# 1_P1.net
KiCad netlist of a schematic drawn in Altium Designer
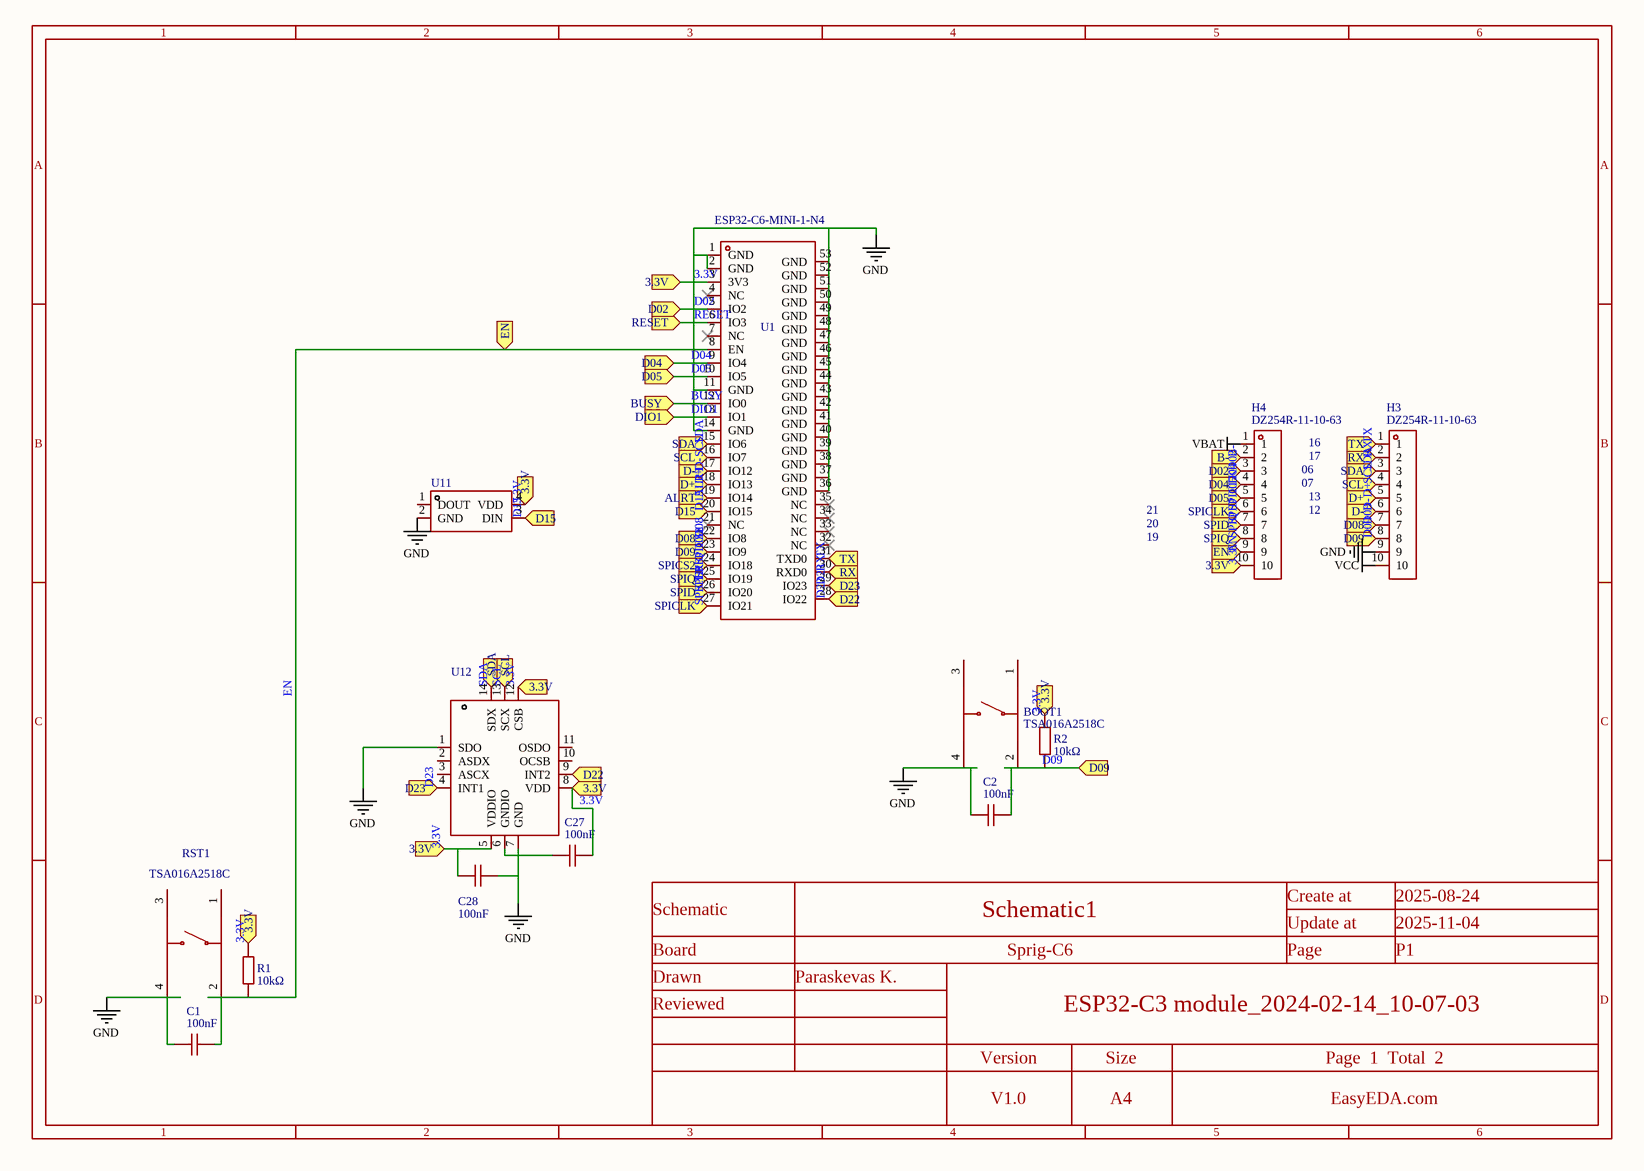
[diagram p0: 1_P1.schdoc]

(export (version "E")
  (design (tool "Eeschema 10.0.6"))
  (components
    (comp (ref "BOOT1")
      (value "TSA016A2518C")
      (footprint "SW-SMD_4P-L4.2-W3.3-P2.15-LS4.6")
      (fields (field (name "MANUFACTURER") "BZCN(博众电气)"))
      (libsource (lib "altium-import") (part "root_3_TSA016A2518C_"))
    )
    (comp (ref "C1")
      (value "100nF")
      (footprint "C0402")
      (fields
        (field (name "MANUFACTURER") "FH(风华)")
        (field (name "MANUFACTURER PART") "0402B104K160NT")
        (field (name "TOLERANCE") "±10%")
      )
      (libsource (lib "altium-import") (part "root_0_0402B104K160NT_"))
    )
    (comp (ref "C2")
      (value "100nF")
      (footprint "C0402")
      (fields
        (field (name "MANUFACTURER") "FH(风华)")
        (field (name "MANUFACTURER PART") "0402B104K160NT")
        (field (name "TOLERANCE") "±10%")
      )
      (libsource (lib "altium-import") (part "root_0_0402B104K160NT_"))
    )
    (comp (ref "C27")
      (value "100nF")
      (footprint "C0402")
      (fields
        (field (name "MANUFACTURER") "FH(风华)")
        (field (name "MANUFACTURER PART") "0402B104K160NT")
        (field (name "TOLERANCE") "±10%")
      )
      (libsource (lib "altium-import") (part "root_0_0402B104K160NT_"))
    )
    (comp (ref "C28")
      (value "100nF")
      (footprint "C0402")
      (fields
        (field (name "MANUFACTURER") "FH(风华)")
        (field (name "MANUFACTURER PART") "0402B104K160NT")
        (field (name "TOLERANCE") "±10%")
      )
      (libsource (lib "altium-import") (part "root_0_0402B104K160NT_"))
    )
    (comp (ref "H3")
      (value "DZ254R-11-10-63")
      (footprint "HDR-TH_10P-P2.54-V-M")
      (fields (field (name "MANUFACTURER") "DEALON(德艺隆)"))
      (libsource (lib "altium-import") (part "root_0_DZ254R-11-10-63_"))
    )
    (comp (ref "H4")
      (value "DZ254R-11-10-63")
      (footprint "HDR-TH_10P-P2.54-V-M")
      (fields (field (name "MANUFACTURER") "DEALON(德艺隆)"))
      (libsource (lib "altium-import") (part "root_0_DZ254R-11-10-63_"))
    )
    (comp (ref "R1")
      (value "10kΩ")
      (footprint "R0402")
      (fields
        (field (name "MANUFACTURER") "大毅科技")
        (field (name "MANUFACTURER PART") "RMS04FT1002")
        (field (name "TOLERANCE") "±1%")
      )
      (libsource (lib "altium-import") (part "root_1_RMS04FT1002_"))
    )
    (comp (ref "R2")
      (value "10kΩ")
      (footprint "R0402")
      (fields
        (field (name "MANUFACTURER") "大毅科技")
        (field (name "MANUFACTURER PART") "RMS04FT1002")
        (field (name "TOLERANCE") "±1%")
      )
      (libsource (lib "altium-import") (part "root_1_RMS04FT1002_"))
    )
    (comp (ref "RST1")
      (value "TSA016A2518C")
      (footprint "SW-SMD_4P-L4.2-W3.3-P2.15-LS4.6")
      (fields (field (name "MANUFACTURER") "BZCN(博众电气)"))
      (libsource (lib "altium-import") (part "root_3_TSA016A2518C_"))
    )
    (comp (ref "U1")
      (value "ESP32-C6-MINI-1-N4")
      (footprint "WIFIM-SMD_61P-L16.6-W13.2-P0.80-ESP32-C6-MINI-1-N4")
      (fields (field (name "MANUFACTURER") "ESPRESSIF(乐鑫)"))
      (libsource (lib "altium-import") (part "root_0_ESP32-C6-MINI-1-N4_"))
    )
    (comp (ref "U11")
      (value "SK6805D-EC2018")
      (footprint "LED-SMD_4P-L2.0-W1.8-BL_SK6805D")
      (fields (field (name "MANUFACTURER") "欧思科光电"))
      (libsource (lib "altium-import") (part "root_0_SK6805D-EC2018_"))
    )
    (comp (ref "U12")
      (value "BMI260")
      (footprint "LGA-14_L3.0-W2.5-P0.50-TL")
      (fields (field (name "MANUFACTURER") "Bosch(博世)"))
      (libsource (lib "altium-import") (part "root_0_BMI260_"))
    )
  )
  (nets
    (net (code "1") (name "/ALRT") (class "Default")
      (node (ref "U1") (pin "19") (pinfunction "IO14_19") (pintype "passive"))
    )
    (net (code "2") (name "/B-") (class "Default")
      (node (ref "H4") (pin "2") (pinfunction "2_2") (pintype "passive"))
    )
    (net (code "3") (name "/BUSY") (class "Default")
      (node (ref "U1") (pin "12") (pinfunction "IO0_12") (pintype "passive"))
    )
    (net (code "4") (name "/D+") (class "Default")
      (node (ref "H3") (pin "5") (pinfunction "5_5") (pintype "passive"))
      (node (ref "U1") (pin "18") (pinfunction "IO13_18") (pintype "passive"))
    )
    (net (code "5") (name "/D-") (class "Default")
      (node (ref "H3") (pin "6") (pinfunction "6_6") (pintype "passive"))
      (node (ref "U1") (pin "17") (pinfunction "IO12_17") (pintype "passive"))
    )
    (net (code "6") (name "/D04") (class "Default")
      (node (ref "H4") (pin "4") (pinfunction "4_4") (pintype "passive"))
      (node (ref "U1") (pin "9") (pinfunction "IO4_9") (pintype "passive"))
    )
    (net (code "7") (name "/D05") (class "Default")
      (node (ref "H4") (pin "5") (pinfunction "5_5") (pintype "passive"))
      (node (ref "U1") (pin "10") (pinfunction "IO5_10") (pintype "passive"))
    )
    (net (code "8") (name "/D08") (class "Default")
      (node (ref "H3") (pin "7") (pinfunction "7_7") (pintype "passive"))
      (node (ref "U1") (pin "22") (pinfunction "IO8_22") (pintype "passive"))
    )
    (net (code "9") (name "/D09") (class "Default")
      (node (ref "BOOT1") (pin "2") (pinfunction "2_2") (pintype "passive"))
      (node (ref "C2") (pin "2") (pinfunction "2_2") (pintype "passive"))
      (node (ref "H3") (pin "8") (pinfunction "8_8") (pintype "passive"))
      (node (ref "R2") (pin "1") (pinfunction "1_1") (pintype "passive"))
      (node (ref "U1") (pin "23") (pinfunction "IO9_23") (pintype "passive"))
    )
    (net (code "10") (name "/D15") (class "Default")
      (node (ref "U1") (pin "20") (pinfunction "IO15_20") (pintype "passive"))
      (node (ref "U11") (pin "3") (pinfunction "DIN_3") (pintype "passive"))
    )
    (net (code "11") (name "/D22") (class "Default")
      (node (ref "U1") (pin "28") (pinfunction "IO22_28") (pintype "passive"))
      (node (ref "U12") (pin "9") (pinfunction "INT2_9") (pintype "passive"))
    )
    (net (code "12") (name "/D23") (class "Default")
      (node (ref "U1") (pin "29") (pinfunction "IO23_29") (pintype "passive"))
      (node (ref "U12") (pin "4") (pinfunction "INT1_4") (pintype "passive"))
    )
    (net (code "13") (name "/DIO1") (class "Default")
      (node (ref "U1") (pin "13") (pinfunction "IO1_13") (pintype "passive"))
    )
    (net (code "14") (name "/EN") (class "Default")
      (node (ref "C1") (pin "2") (pinfunction "2_2") (pintype "passive"))
      (node (ref "H4") (pin "9") (pinfunction "9_9") (pintype "passive"))
      (node (ref "R1") (pin "1") (pinfunction "1_1") (pintype "passive"))
      (node (ref "RST1") (pin "2") (pinfunction "2_2") (pintype "passive"))
      (node (ref "U1") (pin "8") (pinfunction "EN_8") (pintype "passive"))
    )
    (net (code "15") (name "/RX") (class "Default")
      (node (ref "H3") (pin "2") (pinfunction "2_2") (pintype "passive"))
      (node (ref "U1") (pin "30") (pinfunction "RXD0_30") (pintype "passive"))
    )
    (net (code "16") (name "/SCL") (class "Default")
      (node (ref "H3") (pin "4") (pinfunction "4_4") (pintype "passive"))
      (node (ref "U1") (pin "16") (pinfunction "IO7_16") (pintype "passive"))
      (node (ref "U12") (pin "13") (pinfunction "SCX_13") (pintype "passive"))
    )
    (net (code "17") (name "/SDA") (class "Default")
      (node (ref "H3") (pin "3") (pinfunction "3_3") (pintype "passive"))
      (node (ref "U1") (pin "15") (pinfunction "IO6_15") (pintype "passive"))
      (node (ref "U12") (pin "14") (pinfunction "SDX_14") (pintype "passive"))
    )
    (net (code "18") (name "/SPICLK") (class "Default")
      (node (ref "H4") (pin "6") (pinfunction "6_6") (pintype "passive"))
      (node (ref "U1") (pin "27") (pinfunction "IO21_27") (pintype "passive"))
    )
    (net (code "19") (name "/SPICS2") (class "Default")
      (node (ref "U1") (pin "24") (pinfunction "IO18_24") (pintype "passive"))
    )
    (net (code "20") (name "/SPID") (class "Default")
      (node (ref "H4") (pin "7") (pinfunction "7_7") (pintype "passive"))
      (node (ref "U1") (pin "26") (pinfunction "IO20_26") (pintype "passive"))
    )
    (net (code "21") (name "/SPIQ") (class "Default")
      (node (ref "H4") (pin "8") (pinfunction "8_8") (pintype "passive"))
      (node (ref "U1") (pin "25") (pinfunction "IO19_25") (pintype "passive"))
    )
    (net (code "22") (name "/TX") (class "Default")
      (node (ref "H3") (pin "1") (pinfunction "1_1") (pintype "passive"))
      (node (ref "U1") (pin "31") (pinfunction "TXD0_31") (pintype "passive"))
    )
    (net (code "23") (name "GND") (class "Default")
      (node (ref "BOOT1") (pin "4") (pinfunction "4_4") (pintype "passive"))
      (node (ref "C1") (pin "1") (pinfunction "1_1") (pintype "passive"))
      (node (ref "C2") (pin "1") (pinfunction "1_1") (pintype "passive"))
      (node (ref "C27") (pin "1") (pinfunction "1_1") (pintype "passive"))
      (node (ref "C27") (pin "2") (pinfunction "2_2") (pintype "passive"))
      (node (ref "C28") (pin "1") (pinfunction "1_1") (pintype "passive"))
      (node (ref "C28") (pin "2") (pinfunction "2_2") (pintype "passive"))
      (node (ref "H3") (pin "9") (pinfunction "9_9") (pintype "passive"))
      (node (ref "H4") (pin "10") (pinfunction "10_10") (pintype "passive"))
      (node (ref "H4") (pin "3") (pinfunction "3_3") (pintype "passive"))
      (node (ref "R1") (pin "2") (pinfunction "2_2") (pintype "passive"))
      (node (ref "R2") (pin "2") (pinfunction "2_2") (pintype "passive"))
      (node (ref "RST1") (pin "4") (pinfunction "4_4") (pintype "passive"))
      (node (ref "U1") (pin "1") (pinfunction "GND_1") (pintype "passive"))
      (node (ref "U1") (pin "11") (pinfunction "GND_11") (pintype "passive"))
      (node (ref "U1") (pin "14") (pinfunction "GND_14") (pintype "passive"))
      (node (ref "U1") (pin "2") (pinfunction "GND_2") (pintype "passive"))
      (node (ref "U1") (pin "3") (pinfunction "3V3_3") (pintype "passive"))
      (node (ref "U1") (pin "36") (pinfunction "GND_36") (pintype "passive"))
      (node (ref "U1") (pin "37") (pinfunction "GND_37") (pintype "passive"))
      (node (ref "U1") (pin "38") (pinfunction "GND_38") (pintype "passive"))
      (node (ref "U1") (pin "39") (pinfunction "GND_39") (pintype "passive"))
      (node (ref "U1") (pin "40") (pinfunction "GND_40") (pintype "passive"))
      (node (ref "U1") (pin "41") (pinfunction "GND_41") (pintype "passive"))
      (node (ref "U1") (pin "42") (pinfunction "GND_42") (pintype "passive"))
      (node (ref "U1") (pin "43") (pinfunction "GND_43") (pintype "passive"))
      (node (ref "U1") (pin "44") (pinfunction "GND_44") (pintype "passive"))
      (node (ref "U1") (pin "45") (pinfunction "GND_45") (pintype "passive"))
      (node (ref "U1") (pin "46") (pinfunction "GND_46") (pintype "passive"))
      (node (ref "U1") (pin "47") (pinfunction "GND_47") (pintype "passive"))
      (node (ref "U1") (pin "48") (pinfunction "GND_48") (pintype "passive"))
      (node (ref "U1") (pin "49") (pinfunction "GND_49") (pintype "passive"))
      (node (ref "U1") (pin "5") (pinfunction "IO2_5") (pintype "passive"))
      (node (ref "U1") (pin "50") (pinfunction "GND_50") (pintype "passive"))
      (node (ref "U1") (pin "51") (pinfunction "GND_51") (pintype "passive"))
      (node (ref "U1") (pin "52") (pinfunction "GND_52") (pintype "passive"))
      (node (ref "U1") (pin "53") (pinfunction "GND_53") (pintype "passive"))
      (node (ref "U1") (pin "6") (pinfunction "IO3_6") (pintype "passive"))
      (node (ref "U11") (pin "2") (pinfunction "GND_2") (pintype "passive"))
      (node (ref "U11") (pin "4") (pinfunction "VDD_4") (pintype "passive"))
      (node (ref "U12") (pin "1") (pinfunction "SDO_1") (pintype "passive"))
      (node (ref "U12") (pin "12") (pinfunction "CSB_12") (pintype "passive"))
      (node (ref "U12") (pin "5") (pinfunction "VDDIO_5") (pintype "passive"))
      (node (ref "U12") (pin "6") (pinfunction "GNDIO_6") (pintype "passive"))
      (node (ref "U12") (pin "7") (pinfunction "GND_7") (pintype "passive"))
      (node (ref "U12") (pin "8") (pinfunction "VDD_8") (pintype "passive"))
    )
    (net (code "24") (name "VBAT") (class "Default")
      (node (ref "H4") (pin "1") (pinfunction "1_1") (pintype "passive"))
    )
    (net (code "25") (name "VCC") (class "Default")
      (node (ref "H3") (pin "10") (pinfunction "10_10") (pintype "passive"))
    )
    (net (code "26") (name "unconnected-(BOOT1-Pad1)") (class "Default")
      (node (ref "BOOT1") (pin "1") (pinfunction "1_1") (pintype "passive"))
    )
    (net (code "27") (name "unconnected-(BOOT1-Pad3)") (class "Default")
      (node (ref "BOOT1") (pin "3") (pinfunction "3_3") (pintype "passive"))
    )
    (net (code "28") (name "unconnected-(RST1-Pad1)") (class "Default")
      (node (ref "RST1") (pin "1") (pinfunction "1_1") (pintype "passive"))
    )
    (net (code "29") (name "unconnected-(RST1-Pad3)") (class "Default")
      (node (ref "RST1") (pin "3") (pinfunction "3_3") (pintype "passive"))
    )
    (net (code "30") (name "unconnected-(U1-NC-Pad4)") (class "Default")
      (node (ref "U1") (pin "4") (pinfunction "NC_4") (pintype "passive+no_connect"))
    )
    (net (code "31") (name "unconnected-(U1-NC-Pad7)") (class "Default")
      (node (ref "U1") (pin "7") (pinfunction "NC_7") (pintype "passive+no_connect"))
    )
    (net (code "32") (name "unconnected-(U1-NC-Pad21)") (class "Default")
      (node (ref "U1") (pin "21") (pinfunction "NC_21") (pintype "passive+no_connect"))
    )
    (net (code "33") (name "unconnected-(U1-NC-Pad32)") (class "Default")
      (node (ref "U1") (pin "32") (pinfunction "NC_32") (pintype "passive+no_connect"))
    )
    (net (code "34") (name "unconnected-(U1-NC-Pad33)") (class "Default")
      (node (ref "U1") (pin "33") (pinfunction "NC_33") (pintype "passive+no_connect"))
    )
    (net (code "35") (name "unconnected-(U1-NC-Pad34)") (class "Default")
      (node (ref "U1") (pin "34") (pinfunction "NC_34") (pintype "passive+no_connect"))
    )
    (net (code "36") (name "unconnected-(U1-NC-Pad35)") (class "Default")
      (node (ref "U1") (pin "35") (pinfunction "NC_35") (pintype "passive+no_connect"))
    )
    (net (code "37") (name "unconnected-(U11-DOUT-Pad1)") (class "Default")
      (node (ref "U11") (pin "1") (pinfunction "DOUT_1") (pintype "passive"))
    )
    (net (code "38") (name "unconnected-(U12-ASCX-Pad3)") (class "Default")
      (node (ref "U12") (pin "3") (pinfunction "ASCX_3") (pintype "passive"))
    )
    (net (code "39") (name "unconnected-(U12-ASDX-Pad2)") (class "Default")
      (node (ref "U12") (pin "2") (pinfunction "ASDX_2") (pintype "passive"))
    )
    (net (code "40") (name "unconnected-(U12-OCSB-Pad10)") (class "Default")
      (node (ref "U12") (pin "10") (pinfunction "OCSB_10") (pintype "passive"))
    )
    (net (code "41") (name "unconnected-(U12-OSDO-Pad11)") (class "Default")
      (node (ref "U12") (pin "11") (pinfunction "OSDO_11") (pintype "passive"))
    )
  )
)
